# legatus.net
KiCad netlist of a schematic drawn in EAGLE
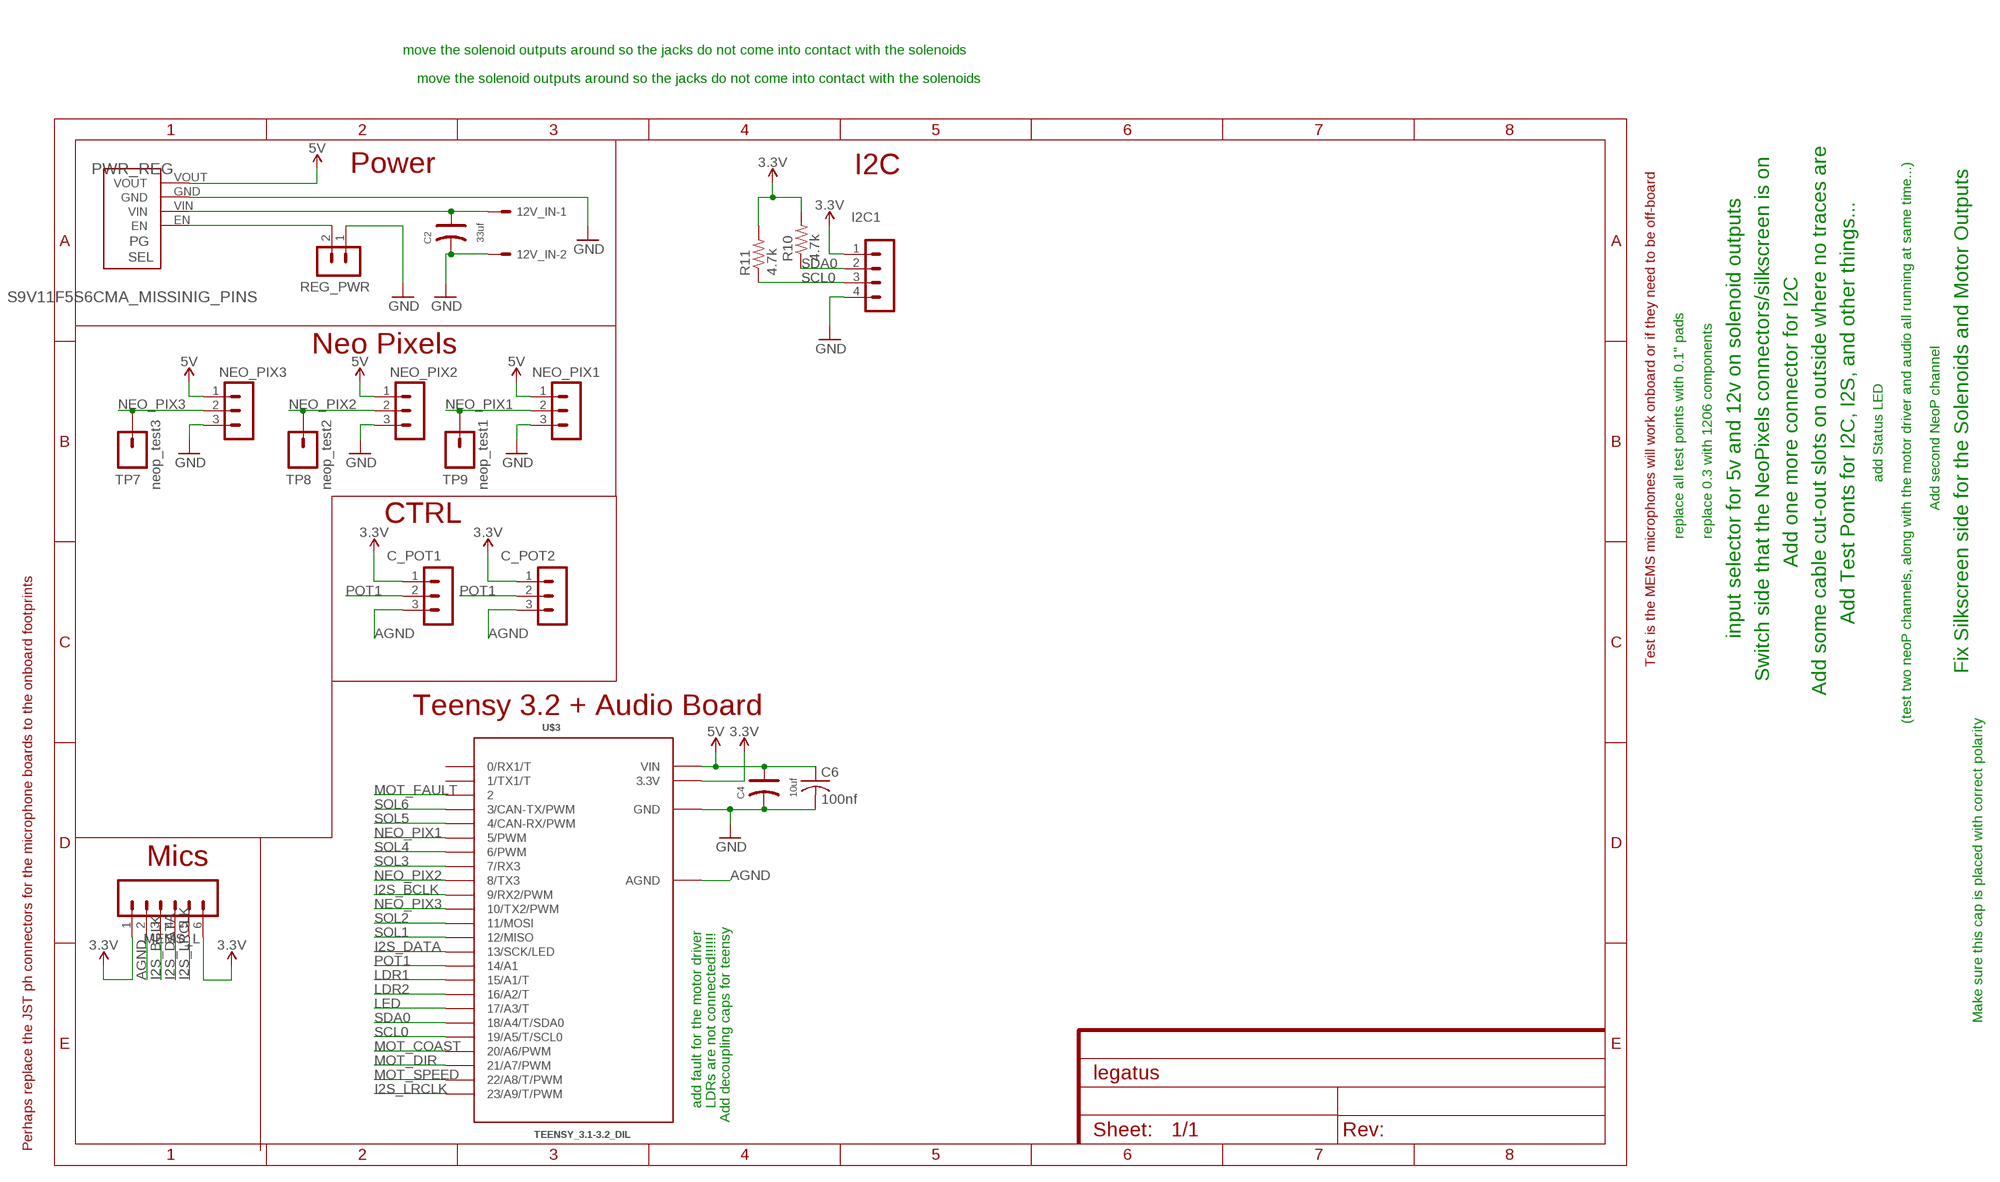
[diagram p0: schematic, sheet 1]

(export (version "E")
  (design (tool "Eeschema 10.0.6"))
  (components
    (comp (ref "12V_IN")
      (value "5566-2")
      (footprint "eagle-import:5566-2")
      (fields (field (name "MF") "MOLEX"))
      (libsource (lib "eagle-import") (part "5566-2"))
    )
    (comp (ref "C2")
      (value "33uf")
      (footprint "eagle-import:PC-D5.3MM")
      (fields (field (name "MPN") "KS 100uF/16V"))
      (libsource (lib "eagle-import") (part "DIP-ALUMINUM-47UF-16V(D5-H7MM)"))
    )
    (comp (ref "C4")
      (value "10uf")
      (footprint "eagle-import:PC-D5.3MM")
      (fields (field (name "MPN") "KS 100uF/16V"))
      (libsource (lib "eagle-import") (part "DIP-ALUMINUM-47UF-16V(D5-H7MM)"))
    )
    (comp (ref "C6")
      (value "100nf")
      (footprint "eagle-import:C2012")
      (libsource (lib "eagle-import") (part "C-USC2012"))
    )
    (comp (ref "C_POT1")
      (value "B3B-PH-K")
      (footprint "eagle-import:B3B-PH-K")
      (libsource (lib "eagle-import") (part "B3B-PH-K"))
    )
    (comp (ref "C_POT2")
      (value "B3B-PH-K")
      (footprint "eagle-import:B3B-PH-K")
      (libsource (lib "eagle-import") (part "B3B-PH-K"))
    )
    (comp (ref "I2C1")
      (value "B4B-PH-K")
      (footprint "eagle-import:B4B-PH-K")
      (libsource (lib "eagle-import") (part "B4B-PH-K"))
    )
    (comp (ref "MEMS_L")
      (value "CONN_06POLAR")
      (footprint "eagle-import:MOLEX-1X6")
      (libsource (lib "eagle-import") (part "CONN_06POLAR"))
    )
    (comp (ref "NEO_PIX1")
      (value "B3B-PH-K")
      (footprint "eagle-import:B3B-PH-K")
      (libsource (lib "eagle-import") (part "B3B-PH-K"))
    )
    (comp (ref "NEO_PIX2")
      (value "B3B-PH-K")
      (footprint "eagle-import:B3B-PH-K")
      (libsource (lib "eagle-import") (part "B3B-PH-K"))
    )
    (comp (ref "NEO_PIX3")
      (value "B3B-PH-K")
      (footprint "eagle-import:B3B-PH-K")
      (libsource (lib "eagle-import") (part "B3B-PH-K"))
    )
    (comp (ref "PWR_REG")
      (value "S9V11F5S6CMA_MISSINIG_PINS")
      (footprint "eagle-import:S9V11F3S5CMA_MISSING_PINS")
      (libsource (lib "eagle-import") (part "S9V11F5S6CMA_MISSINIG_PINS"))
    )
    (comp (ref "R10")
      (value "4.7k")
      (footprint "eagle-import:M1206")
      (libsource (lib "eagle-import") (part "R-US_M1206"))
    )
    (comp (ref "R11")
      (value "4.7k")
      (footprint "eagle-import:M1206")
      (libsource (lib "eagle-import") (part "R-US_M1206"))
    )
    (comp (ref "REG_PWR")
      (value "B2B-PH-K")
      (footprint "eagle-import:B2B-PH-K")
      (libsource (lib "eagle-import") (part "B2B-PH-K"))
    )
    (comp (ref "TP7")
      (value "neop_test3")
      (footprint "eagle-import:1X01")
      (libsource (lib "eagle-import") (part "CONN_01"))
    )
    (comp (ref "TP8")
      (value "neop_test2")
      (footprint "eagle-import:1X01")
      (libsource (lib "eagle-import") (part "CONN_01"))
    )
    (comp (ref "TP9")
      (value "neop_test1")
      (footprint "eagle-import:1X01")
      (libsource (lib "eagle-import") (part "CONN_01"))
    )
    (comp (ref "U$3")
      (value "TEENSY_3.1-3.2_DIL")
      (footprint "eagle-import:TEENSY_3.0-3.2&LC_DIL")
      (libsource (lib "eagle-import") (part "TEENSY_3.1-3.2_DIL"))
    )
  )
  (nets
    (net (code "1") (name "/AGND") (class "Default")
      (node (ref "C_POT1") (pin "3") (pinfunction "3_3") (pintype "passive"))
      (node (ref "C_POT2") (pin "3") (pinfunction "3_3") (pintype "passive"))
      (node (ref "MEMS_L") (pin "2") (pinfunction "2_2") (pintype "passive"))
      (node (ref "U$3") (pin "AGND") (pinfunction "AGND_AGND") (pintype "power_in"))
    )
    (net (code "2") (name "/I2S_BCLK") (class "Default")
      (node (ref "MEMS_L") (pin "3") (pinfunction "3_3") (pintype "passive"))
      (node (ref "U$3") (pin "9") (pinfunction "9/RX2/PWM_9") (pintype "bidirectional"))
    )
    (net (code "3") (name "/I2S_DATA") (class "Default")
      (node (ref "MEMS_L") (pin "4") (pinfunction "4_4") (pintype "passive"))
      (node (ref "U$3") (pin "13") (pinfunction "13/SCK/LED_13") (pintype "bidirectional"))
    )
    (net (code "4") (name "/I2S_LRCLK") (class "Default")
      (node (ref "MEMS_L") (pin "5") (pinfunction "5_5") (pintype "passive"))
      (node (ref "U$3") (pin "23/A9") (pinfunction "23/A9/T/PWM_23/A9") (pintype "bidirectional"))
    )
    (net (code "5") (name "/LDR1") (class "Default")
      (node (ref "U$3") (pin "15/A1") (pinfunction "15/A1/T_15/A1") (pintype "bidirectional"))
    )
    (net (code "6") (name "/LDR2") (class "Default")
      (node (ref "U$3") (pin "16/A2") (pinfunction "16/A2/T_16/A2") (pintype "bidirectional"))
    )
    (net (code "7") (name "/LED") (class "Default")
      (node (ref "U$3") (pin "17/A3") (pinfunction "17/A3/T_17/A3") (pintype "bidirectional"))
    )
    (net (code "8") (name "/MOT_COAST") (class "Default")
      (node (ref "U$3") (pin "20/A6") (pinfunction "20/A6/PWM_20/A6") (pintype "bidirectional"))
    )
    (net (code "9") (name "/MOT_DIR") (class "Default")
      (node (ref "U$3") (pin "21/A7") (pinfunction "21/A7/PWM_21/A7") (pintype "bidirectional"))
    )
    (net (code "10") (name "/MOT_FAULT") (class "Default")
      (node (ref "U$3") (pin "2") (pinfunction "2_2") (pintype "bidirectional"))
    )
    (net (code "11") (name "/MOT_SPEED") (class "Default")
      (node (ref "U$3") (pin "22/A8") (pinfunction "22/A8/T/PWM_22/A8") (pintype "bidirectional"))
    )
    (net (code "12") (name "/NEO_PIX1") (class "Default")
      (node (ref "NEO_PIX1") (pin "2") (pinfunction "2_2") (pintype "passive"))
      (node (ref "TP9") (pin "1") (pinfunction "1_1") (pintype "passive"))
      (node (ref "U$3") (pin "5") (pinfunction "5/PWM_5") (pintype "bidirectional"))
    )
    (net (code "13") (name "/NEO_PIX2") (class "Default")
      (node (ref "NEO_PIX2") (pin "2") (pinfunction "2_2") (pintype "passive"))
      (node (ref "TP8") (pin "1") (pinfunction "1_1") (pintype "passive"))
      (node (ref "U$3") (pin "8") (pinfunction "8/TX3_8") (pintype "bidirectional"))
    )
    (net (code "14") (name "/NEO_PIX3") (class "Default")
      (node (ref "NEO_PIX3") (pin "2") (pinfunction "2_2") (pintype "passive"))
      (node (ref "TP7") (pin "1") (pinfunction "1_1") (pintype "passive"))
      (node (ref "U$3") (pin "10") (pinfunction "10/TX2/PWM_10") (pintype "bidirectional"))
    )
    (net (code "15") (name "/POT1") (class "Default")
      (node (ref "C_POT1") (pin "2") (pinfunction "2_2") (pintype "passive"))
      (node (ref "C_POT2") (pin "2") (pinfunction "2_2") (pintype "passive"))
      (node (ref "U$3") (pin "14/A0") (pinfunction "14/A1_14/A0") (pintype "bidirectional"))
    )
    (net (code "16") (name "/SCL0") (class "Default")
      (node (ref "I2C1") (pin "3") (pinfunction "3_3") (pintype "passive"))
      (node (ref "R11") (pin "1") (pinfunction "1_1") (pintype "passive"))
      (node (ref "U$3") (pin "19/A5") (pinfunction "19/A5/T/SCL0_19/A5") (pintype "bidirectional"))
    )
    (net (code "17") (name "/SDA0") (class "Default")
      (node (ref "I2C1") (pin "2") (pinfunction "2_2") (pintype "passive"))
      (node (ref "R10") (pin "1") (pinfunction "1_1") (pintype "passive"))
      (node (ref "U$3") (pin "18/A4") (pinfunction "18/A4/T/SDA0_18/A4") (pintype "bidirectional"))
    )
    (net (code "18") (name "/SOL1") (class "Default")
      (node (ref "U$3") (pin "12") (pinfunction "12/MISO_12") (pintype "bidirectional"))
    )
    (net (code "19") (name "/SOL2") (class "Default")
      (node (ref "U$3") (pin "11") (pinfunction "11/MOSI_11") (pintype "bidirectional"))
    )
    (net (code "20") (name "/SOL3") (class "Default")
      (node (ref "U$3") (pin "7") (pinfunction "7/RX3_7") (pintype "bidirectional"))
    )
    (net (code "21") (name "/SOL4") (class "Default")
      (node (ref "U$3") (pin "6") (pinfunction "6/PWM_6") (pintype "bidirectional"))
    )
    (net (code "22") (name "/SOL5") (class "Default")
      (node (ref "U$3") (pin "4") (pinfunction "4/CAN-RX/PWM_4") (pintype "bidirectional"))
    )
    (net (code "23") (name "/SOL6") (class "Default")
      (node (ref "U$3") (pin "3") (pinfunction "3/CAN-TX/PWM_3") (pintype "bidirectional"))
    )
    (net (code "24") (name "3.3V") (class "Default")
      (node (ref "C_POT1") (pin "1") (pinfunction "1_1") (pintype "passive"))
      (node (ref "C_POT2") (pin "1") (pinfunction "1_1") (pintype "passive"))
      (node (ref "I2C1") (pin "1") (pinfunction "1_1") (pintype "passive"))
      (node (ref "MEMS_L") (pin "1") (pinfunction "1_1") (pintype "passive"))
      (node (ref "MEMS_L") (pin "6") (pinfunction "6_6") (pintype "passive"))
      (node (ref "R10") (pin "2") (pinfunction "2_2") (pintype "passive"))
      (node (ref "R11") (pin "2") (pinfunction "2_2") (pintype "passive"))
      (node (ref "U$3") (pin "3.3V") (pinfunction "3.3V_3.3V") (pintype "power_in"))
    )
    (net (code "25") (name "5V") (class "Default")
      (node (ref "C4") (pin "+") (pinfunction "+_+") (pintype "passive"))
      (node (ref "C6") (pin "1") (pinfunction "1_1") (pintype "passive"))
      (node (ref "NEO_PIX1") (pin "1") (pinfunction "1_1") (pintype "passive"))
      (node (ref "NEO_PIX2") (pin "1") (pinfunction "1_1") (pintype "passive"))
      (node (ref "NEO_PIX3") (pin "1") (pinfunction "1_1") (pintype "passive"))
      (node (ref "PWR_REG") (pin "VOUT") (pinfunction "VOUT_VOUT") (pintype "bidirectional"))
      (node (ref "U$3") (pin "VIN") (pinfunction "VIN_VIN") (pintype "power_in"))
    )
    (net (code "26") (name "GND") (class "Default")
      (node (ref "12V_IN") (pin "2") (pinfunction "S_2") (pintype "passive"))
      (node (ref "C2") (pin "-") (pinfunction "-_-") (pintype "passive"))
      (node (ref "C4") (pin "-") (pinfunction "-_-") (pintype "passive"))
      (node (ref "C6") (pin "2") (pinfunction "2_2") (pintype "passive"))
      (node (ref "I2C1") (pin "4") (pinfunction "4_4") (pintype "passive"))
      (node (ref "NEO_PIX1") (pin "3") (pinfunction "3_3") (pintype "passive"))
      (node (ref "NEO_PIX2") (pin "3") (pinfunction "3_3") (pintype "passive"))
      (node (ref "NEO_PIX3") (pin "3") (pinfunction "3_3") (pintype "passive"))
      (node (ref "PWR_REG") (pin "GND") (pinfunction "GND_GND") (pintype "bidirectional"))
      (node (ref "REG_PWR") (pin "1") (pinfunction "1_1") (pintype "passive"))
      (node (ref "U$3") (pin "GND") (pinfunction "GND_GND") (pintype "power_in"))
    )
    (net (code "27") (name "Net-(12V_INA-S)") (class "Default")
      (node (ref "12V_IN") (pin "1") (pinfunction "S_1") (pintype "passive"))
      (node (ref "C2") (pin "+") (pinfunction "+_+") (pintype "passive"))
      (node (ref "PWR_REG") (pin "VIN") (pinfunction "VIN_VIN") (pintype "bidirectional"))
    )
    (net (code "28") (name "Net-(PWR_REG-PadEN)") (class "Default")
      (node (ref "PWR_REG") (pin "EN") (pinfunction "EN_EN") (pintype "bidirectional"))
      (node (ref "REG_PWR") (pin "2") (pinfunction "2_2") (pintype "passive"))
    )
    (net (code "29") (name "unconnected-(U$3-0{slash}RX1{slash}T-Pad0)") (class "Default")
      (node (ref "U$3") (pin "0") (pinfunction "0/RX1/T_0") (pintype "bidirectional"))
    )
    (net (code "30") (name "unconnected-(U$3-1{slash}TX1{slash}T-Pad1)") (class "Default")
      (node (ref "U$3") (pin "1") (pinfunction "1/TX1/T_1") (pintype "bidirectional"))
    )
  )
)
